# Grid_Lock.net
KiCad netlist of a schematic drawn in Altium Designer
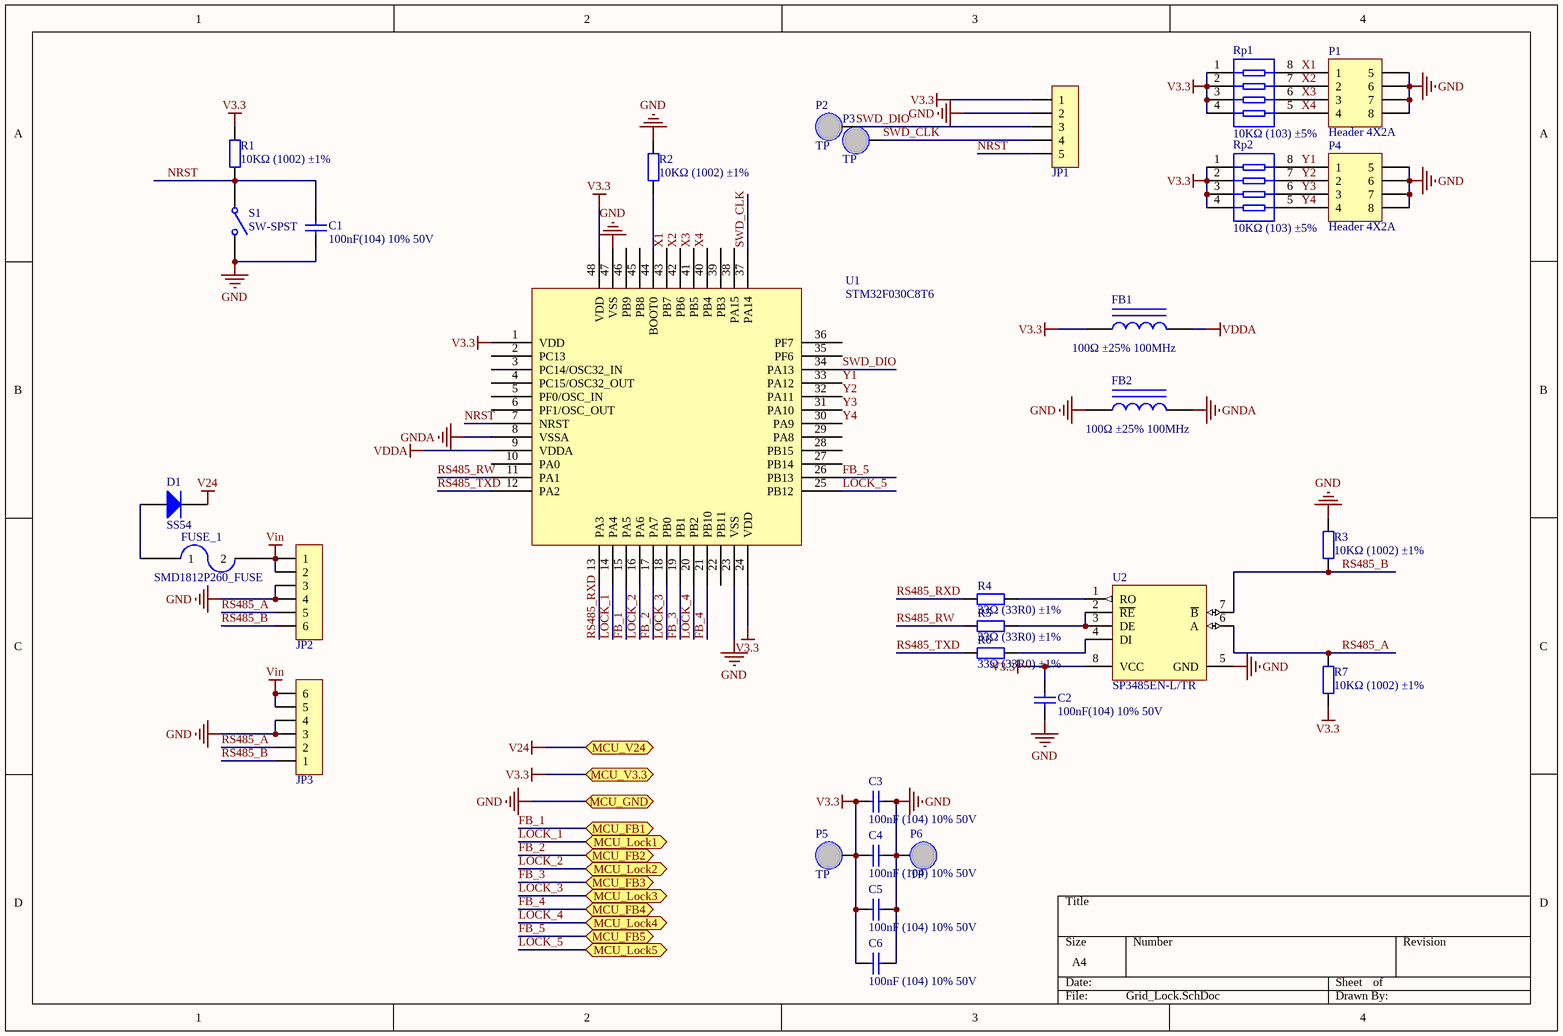
[diagram p0: Grid_Lock.SchDoc]

(export (version "E")
  (design (tool "Eeschema 10.0.6"))
  (components
    (comp (ref "C1")
      (value "100nF(104) 10% 50V")
      (footprint "0805_C")
      (description "贴片电容")
      (libsource (lib "Miscellaneous Devices LC") (part "0805 100nF(104) 10% 50V"))
    )
    (comp (ref "C2")
      (value "100nF(104) 10% 50V")
      (footprint "0805_C")
      (description "贴片电容")
      (libsource (lib "Miscellaneous Devices LC") (part "0805 100nF(104) 10% 50V"))
    )
    (comp (ref "C3")
      (value "100nF (104) 10% 50V")
      (footprint "0603_C")
      (description "贴片电容")
      (libsource (lib "Miscellaneous Devices LC") (part "0603 100nF (104) 10% 50V"))
    )
    (comp (ref "C4")
      (value "100nF (104) 10% 50V")
      (footprint "0603_C")
      (description "贴片电容")
      (libsource (lib "Miscellaneous Devices LC") (part "0603 100nF (104) 10% 50V"))
    )
    (comp (ref "C5")
      (value "100nF (104) 10% 50V")
      (footprint "0603_C")
      (description "贴片电容")
      (libsource (lib "Miscellaneous Devices LC") (part "0603 100nF (104) 10% 50V"))
    )
    (comp (ref "C6")
      (value "100nF (104) 10% 50V")
      (footprint "0603_C")
      (description "贴片电容")
      (libsource (lib "Miscellaneous Devices LC") (part "0603 100nF (104) 10% 50V"))
    )
    (comp (ref "D1")
      (value "SS54")
      (footprint "SMA(DO-214AC)_S1")
      (description "二极管")
      (libsource (lib "Miscellaneous Devices LC") (part "SMA(DO-214AC) SS54"))
    )
    (comp (ref "FB1")
      (value "100Ω ±25% 100MHz")
      (footprint "0805_L")
      (description "贴片磁珠")
      (libsource (lib "Miscellaneous Devices LC") (part "0805 100Ω 25% 100MHz"))
    )
    (comp (ref "FB2")
      (value "100Ω ±25% 100MHz")
      (footprint "0805_L")
      (description "贴片磁珠")
      (libsource (lib "Miscellaneous Devices LC") (part "0805 100Ω 25% 100MHz"))
    )
    (comp (ref "FUSE_1")
      (value "SMD1812P260_FUSE")
      (footprint "SMD1812P260")
      (libsource (lib "mylib") (part "SMD1812P260_FUSE"))
    )
    (comp (ref "JP1")
      (value "HDR-1X5")
      (footprint "XH2.54-WS-5P")
      (description "5P接插件")
      (fields (field (name "版权归属") "源创客"))
      (libsource (lib "4.5   - 接插件-脚距2.54") (part "Header 5"))
    )
    (comp (ref "JP2")
      (value "HDR-1X6")
      (footprint "XH2.54-WS-6P")
      (description "6P接插件")
      (fields (field (name "版权归属") "源创客"))
      (libsource (lib "4.5   - 接插件-脚距2.54") (part "Header 6"))
    )
    (comp (ref "JP3")
      (value "HDR-1X6")
      (footprint "XH2.54-WS-6P")
      (description "6P接插件")
      (fields (field (name "版权归属") "源创客"))
      (libsource (lib "") (part "Header 6_1"))
    )
    (comp (ref "P1")
      (value "Header 4X2A")
      (footprint "HDR2X4_CEN")
      (description "Header, 4-Pin, Dual row")
      (fields (field (name "PUBLISHER") "Altium Limited"))
      (libsource (lib "Miscellaneous Connectors") (part "Header 4X2A"))
    )
    (comp (ref "P2") (value "TP") (libsource (lib "mylib") (part "TP")))
    (comp (ref "P3") (value "TP") (libsource (lib "mylib") (part "TP")))
    (comp (ref "P4")
      (value "Header 4X2A")
      (footprint "HDR2X4_CEN")
      (description "Header, 4-Pin, Dual row")
      (fields (field (name "PUBLISHER") "Altium Limited"))
      (libsource (lib "Miscellaneous Connectors") (part "Header 4X2A"))
    )
    (comp (ref "P5") (value "TP") (libsource (lib "mylib") (part "TP")))
    (comp (ref "P6") (value "TP") (libsource (lib "mylib") (part "TP")))
    (comp (ref "R1")
      (value "10KΩ (1002) ±1%")
      (footprint "0805_R")
      (description "贴片电阻")
      (libsource (lib "Miscellaneous Devices LC") (part "0805 10KΩ (1002) 1%"))
    )
    (comp (ref "R2")
      (value "10KΩ (1002) ±1%")
      (footprint "0805_R")
      (description "贴片电阻")
      (libsource (lib "Miscellaneous Devices LC") (part "0805 10KΩ (1002) 1%"))
    )
    (comp (ref "R3")
      (value "10KΩ (1002) ±1%")
      (footprint "0805_R")
      (description "贴片电阻")
      (libsource (lib "Miscellaneous Devices LC") (part "0805 10KΩ (1002) 1%"))
    )
    (comp (ref "R4")
      (value "33Ω (33R0) ±1%")
      (footprint "0603_R")
      (description "贴片电阻")
      (libsource (lib "Miscellaneous Devices LC") (part "0603 33Ω (33R0) 1%"))
    )
    (comp (ref "R5")
      (value "33Ω (33R0) ±1%")
      (footprint "0603_R")
      (description "贴片电阻")
      (libsource (lib "Miscellaneous Devices LC") (part "0603 33Ω (33R0) 1%"))
    )
    (comp (ref "R6")
      (value "33Ω (33R0) ±1%")
      (footprint "0603_R")
      (description "贴片电阻")
      (libsource (lib "Miscellaneous Devices LC") (part "0603 33Ω (33R0) 1%"))
    )
    (comp (ref "R7")
      (value "10KΩ (1002) ±1%")
      (footprint "0805_R")
      (description "贴片电阻")
      (libsource (lib "Miscellaneous Devices LC") (part "0805 10KΩ (1002) 1%"))
    )
    (comp (ref "Rp1")
      (value "10KΩ (103) ±5%")
      (footprint "0603_Rx4")
      (description "贴片排阻")
      (libsource (lib "Miscellaneous Devices LC") (part "0603*4  10KΩ (103) 5%"))
    )
    (comp (ref "Rp2")
      (value "10KΩ (103) ±5%")
      (footprint "0603_Rx4")
      (description "贴片排阻")
      (libsource (lib "Miscellaneous Devices LC") (part "0603*4  10KΩ (103) 5%"))
    )
    (comp (ref "S1")
      (value "SW-SPST")
      (footprint "key")
      (description "Single-Pole, Single-Throw Switch")
      (fields (field (name "PUBLISHER") "Altium Limited"))
      (libsource (lib "Miscellaneous Devices") (part "SW-SPST"))
    )
    (comp (ref "U1")
      (value "STM32F030C8T6")
      (footprint "LQFP-48_7x7x05P")
      (description "ARM")
      (libsource (lib "Miscellaneous Devices LC") (part "STM32F030C8T6"))
    )
    (comp (ref "U2")
      (value "SP3485EN-L/TR")
      (footprint "SOIC-8_150mil")
      (description "RS-485/RS-422")
      (libsource (lib "Miscellaneous Devices LC") (part "SP3485EN-L/TR_[C8963]"))
    )
  )
  (nets
    (net (code "1") (name "/FB_1") (class "Default")
      (node (ref "U1") (pin "15") (pinfunction "PA5_15") (pintype "passive"))
    )
    (net (code "2") (name "/FB_2") (class "Default")
      (node (ref "U1") (pin "17") (pinfunction "PA7_17") (pintype "passive"))
    )
    (net (code "3") (name "/FB_3") (class "Default")
      (node (ref "U1") (pin "19") (pinfunction "PB1_19") (pintype "passive"))
    )
    (net (code "4") (name "/FB_4") (class "Default")
      (node (ref "U1") (pin "21") (pinfunction "PB10_21") (pintype "passive"))
    )
    (net (code "5") (name "/FB_5") (class "Default")
      (node (ref "U1") (pin "26") (pinfunction "PB13_26") (pintype "passive"))
    )
    (net (code "6") (name "/LOCK_1") (class "Default")
      (node (ref "U1") (pin "14") (pinfunction "PA4_14") (pintype "passive"))
    )
    (net (code "7") (name "/LOCK_2") (class "Default")
      (node (ref "U1") (pin "16") (pinfunction "PA6_16") (pintype "passive"))
    )
    (net (code "8") (name "/LOCK_3") (class "Default")
      (node (ref "U1") (pin "18") (pinfunction "PB0_18") (pintype "passive"))
    )
    (net (code "9") (name "/LOCK_4") (class "Default")
      (node (ref "U1") (pin "20") (pinfunction "PB2_20") (pintype "passive"))
    )
    (net (code "10") (name "/LOCK_5") (class "Default")
      (node (ref "U1") (pin "25") (pinfunction "PB12_25") (pintype "passive"))
    )
    (net (code "11") (name "/NRST") (class "Default")
      (node (ref "C1") (pin "2") (pinfunction "2_2") (pintype "passive"))
      (node (ref "JP1") (pin "5") (pinfunction "5_5") (pintype "passive"))
      (node (ref "R1") (pin "1") (pinfunction "1_1") (pintype "passive"))
      (node (ref "S1") (pin "1") (pinfunction "COMMON_1") (pintype "passive"))
      (node (ref "U1") (pin "7") (pinfunction "NRST_7") (pintype "passive"))
    )
    (net (code "12") (name "/RS485_A") (class "Default")
      (node (ref "JP2") (pin "5") (pinfunction "5_5") (pintype "passive"))
      (node (ref "JP3") (pin "2") (pinfunction "2_2") (pintype "passive"))
      (node (ref "R7") (pin "2") (pinfunction "2_2") (pintype "passive"))
      (node (ref "U2") (pin "6") (pinfunction "A_6") (pintype "bidirectional"))
    )
    (net (code "13") (name "/RS485_B") (class "Default")
      (node (ref "JP2") (pin "6") (pinfunction "6_6") (pintype "passive"))
      (node (ref "JP3") (pin "1") (pinfunction "1_1") (pintype "passive"))
      (node (ref "R3") (pin "1") (pinfunction "1_1") (pintype "passive"))
      (node (ref "U2") (pin "7") (pinfunction "~{B}_7") (pintype "bidirectional"))
    )
    (net (code "14") (name "/RS485_RW") (class "Default")
      (node (ref "R5") (pin "1") (pinfunction "1_1") (pintype "passive"))
      (node (ref "U1") (pin "11") (pinfunction "PA1_11") (pintype "passive"))
    )
    (net (code "15") (name "/RS485_RXD") (class "Default")
      (node (ref "R4") (pin "1") (pinfunction "1_1") (pintype "passive"))
      (node (ref "U1") (pin "13") (pinfunction "PA3_13") (pintype "passive"))
    )
    (net (code "16") (name "/RS485_TXD") (class "Default")
      (node (ref "R6") (pin "1") (pinfunction "1_1") (pintype "passive"))
      (node (ref "U1") (pin "12") (pinfunction "PA2_12") (pintype "passive"))
    )
    (net (code "17") (name "/SWD_CLK") (class "Default")
      (node (ref "JP1") (pin "4") (pinfunction "4_4") (pintype "passive"))
      (node (ref "P3") (pin "1") (pinfunction "1_1") (pintype "passive"))
      (node (ref "U1") (pin "37") (pinfunction "PA14_37") (pintype "passive"))
    )
    (net (code "18") (name "/SWD_DIO") (class "Default")
      (node (ref "JP1") (pin "3") (pinfunction "3_3") (pintype "passive"))
      (node (ref "P2") (pin "1") (pinfunction "1_1") (pintype "passive"))
      (node (ref "U1") (pin "34") (pinfunction "PA13_34") (pintype "passive"))
    )
    (net (code "19") (name "/X1") (class "Default")
      (node (ref "P1") (pin "1") (pinfunction "1_1") (pintype "passive"))
      (node (ref "Rp1") (pin "8") (pinfunction "8_8") (pintype "passive"))
      (node (ref "U1") (pin "43") (pinfunction "PB7_43") (pintype "passive"))
    )
    (net (code "20") (name "/X2") (class "Default")
      (node (ref "P1") (pin "2") (pinfunction "2_2") (pintype "passive"))
      (node (ref "Rp1") (pin "7") (pinfunction "7_7") (pintype "passive"))
      (node (ref "U1") (pin "42") (pinfunction "PB6_42") (pintype "passive"))
    )
    (net (code "21") (name "/X3") (class "Default")
      (node (ref "P1") (pin "3") (pinfunction "3_3") (pintype "passive"))
      (node (ref "Rp1") (pin "6") (pinfunction "6_6") (pintype "passive"))
      (node (ref "U1") (pin "41") (pinfunction "PB5_41") (pintype "passive"))
    )
    (net (code "22") (name "/X4") (class "Default")
      (node (ref "P1") (pin "4") (pinfunction "4_4") (pintype "passive"))
      (node (ref "Rp1") (pin "5") (pinfunction "5_5") (pintype "passive"))
      (node (ref "U1") (pin "40") (pinfunction "PB4_40") (pintype "passive"))
    )
    (net (code "23") (name "/Y1") (class "Default")
      (node (ref "P4") (pin "1") (pinfunction "1_1") (pintype "passive"))
      (node (ref "Rp2") (pin "8") (pinfunction "8_8") (pintype "passive"))
      (node (ref "U1") (pin "33") (pinfunction "PA12_33") (pintype "passive"))
    )
    (net (code "24") (name "/Y2") (class "Default")
      (node (ref "P4") (pin "2") (pinfunction "2_2") (pintype "passive"))
      (node (ref "Rp2") (pin "7") (pinfunction "7_7") (pintype "passive"))
      (node (ref "U1") (pin "32") (pinfunction "PA11_32") (pintype "passive"))
    )
    (net (code "25") (name "/Y3") (class "Default")
      (node (ref "P4") (pin "3") (pinfunction "3_3") (pintype "passive"))
      (node (ref "Rp2") (pin "6") (pinfunction "6_6") (pintype "passive"))
      (node (ref "U1") (pin "31") (pinfunction "PA10_31") (pintype "passive"))
    )
    (net (code "26") (name "/Y4") (class "Default")
      (node (ref "P4") (pin "4") (pinfunction "4_4") (pintype "passive"))
      (node (ref "Rp2") (pin "5") (pinfunction "5_5") (pintype "passive"))
      (node (ref "U1") (pin "30") (pinfunction "PA9_30") (pintype "passive"))
    )
    (net (code "27") (name "GND") (class "Default")
      (node (ref "C1") (pin "1") (pinfunction "1_1") (pintype "passive"))
      (node (ref "C2") (pin "1") (pinfunction "1_1") (pintype "passive"))
      (node (ref "C3") (pin "2") (pinfunction "2_2") (pintype "passive"))
      (node (ref "C4") (pin "2") (pinfunction "2_2") (pintype "passive"))
      (node (ref "C5") (pin "2") (pinfunction "2_2") (pintype "passive"))
      (node (ref "C6") (pin "2") (pinfunction "2_2") (pintype "passive"))
      (node (ref "FB2") (pin "1") (pinfunction "1_1") (pintype "passive"))
      (node (ref "JP1") (pin "2") (pinfunction "2_2") (pintype "passive"))
      (node (ref "JP2") (pin "3") (pinfunction "3_3") (pintype "passive"))
      (node (ref "JP2") (pin "4") (pinfunction "4_4") (pintype "passive"))
      (node (ref "JP3") (pin "3") (pinfunction "3_3") (pintype "passive"))
      (node (ref "JP3") (pin "4") (pinfunction "4_4") (pintype "passive"))
      (node (ref "P1") (pin "5") (pinfunction "5_5") (pintype "passive"))
      (node (ref "P1") (pin "6") (pinfunction "6_6") (pintype "passive"))
      (node (ref "P1") (pin "7") (pinfunction "7_7") (pintype "passive"))
      (node (ref "P1") (pin "8") (pinfunction "8_8") (pintype "passive"))
      (node (ref "P4") (pin "5") (pinfunction "5_5") (pintype "passive"))
      (node (ref "P4") (pin "6") (pinfunction "6_6") (pintype "passive"))
      (node (ref "P4") (pin "7") (pinfunction "7_7") (pintype "passive"))
      (node (ref "P4") (pin "8") (pinfunction "8_8") (pintype "passive"))
      (node (ref "P6") (pin "1") (pinfunction "1_1") (pintype "passive"))
      (node (ref "R2") (pin "2") (pinfunction "2_2") (pintype "passive"))
      (node (ref "R3") (pin "2") (pinfunction "2_2") (pintype "passive"))
      (node (ref "S1") (pin "2") (pinfunction "NO_2") (pintype "passive"))
      (node (ref "U1") (pin "23") (pinfunction "VSS_23") (pintype "passive"))
      (node (ref "U1") (pin "47") (pinfunction "VSS_47") (pintype "passive"))
      (node (ref "U2") (pin "5") (pinfunction "GND_5") (pintype "power_in"))
    )
    (net (code "28") (name "GNDA") (class "Default")
      (node (ref "FB2") (pin "2") (pinfunction "2_2") (pintype "passive"))
      (node (ref "U1") (pin "8") (pinfunction "VSSA_8") (pintype "passive"))
    )
    (net (code "29") (name "Net-(D1-A)") (class "Default")
      (node (ref "D1") (pin "1") (pinfunction "A_1") (pintype "passive"))
      (node (ref "FUSE_1") (pin "1") (pinfunction "1_1") (pintype "passive"))
    )
    (net (code "30") (name "Net-(U1-BOOT0)") (class "Default")
      (node (ref "R2") (pin "1") (pinfunction "1_1") (pintype "passive"))
      (node (ref "U1") (pin "44") (pinfunction "BOOT0_44") (pintype "passive"))
    )
    (net (code "31") (name "Net-(U2-DE)") (class "Default")
      (node (ref "R5") (pin "2") (pinfunction "2_2") (pintype "passive"))
      (node (ref "U2") (pin "2") (pinfunction "~{RE}_2") (pintype "passive"))
      (node (ref "U2") (pin "3") (pinfunction "DE_3") (pintype "passive"))
    )
    (net (code "32") (name "Net-(U2-DI)") (class "Default")
      (node (ref "R6") (pin "2") (pinfunction "2_2") (pintype "passive"))
      (node (ref "U2") (pin "4") (pinfunction "DI_4") (pintype "passive"))
    )
    (net (code "33") (name "Net-(U2-RO)") (class "Default")
      (node (ref "R4") (pin "2") (pinfunction "2_2") (pintype "passive"))
      (node (ref "U2") (pin "1") (pinfunction "RO_1") (pintype "output"))
    )
    (net (code "34") (name "V3.3") (class "Default")
      (node (ref "C2") (pin "2") (pinfunction "2_2") (pintype "passive"))
      (node (ref "C3") (pin "1") (pinfunction "1_1") (pintype "passive"))
      (node (ref "C4") (pin "1") (pinfunction "1_1") (pintype "passive"))
      (node (ref "C5") (pin "1") (pinfunction "1_1") (pintype "passive"))
      (node (ref "C6") (pin "1") (pinfunction "1_1") (pintype "passive"))
      (node (ref "FB1") (pin "1") (pinfunction "1_1") (pintype "passive"))
      (node (ref "JP1") (pin "1") (pinfunction "1_1") (pintype "passive"))
      (node (ref "P5") (pin "1") (pinfunction "1_1") (pintype "passive"))
      (node (ref "R1") (pin "2") (pinfunction "2_2") (pintype "passive"))
      (node (ref "R7") (pin "1") (pinfunction "1_1") (pintype "passive"))
      (node (ref "Rp1") (pin "1") (pinfunction "1_1") (pintype "passive"))
      (node (ref "Rp1") (pin "2") (pinfunction "2_2") (pintype "passive"))
      (node (ref "Rp1") (pin "3") (pinfunction "3_3") (pintype "passive"))
      (node (ref "Rp1") (pin "4") (pinfunction "4_4") (pintype "passive"))
      (node (ref "Rp2") (pin "1") (pinfunction "1_1") (pintype "passive"))
      (node (ref "Rp2") (pin "2") (pinfunction "2_2") (pintype "passive"))
      (node (ref "Rp2") (pin "3") (pinfunction "3_3") (pintype "passive"))
      (node (ref "Rp2") (pin "4") (pinfunction "4_4") (pintype "passive"))
      (node (ref "U1") (pin "1") (pinfunction "VDD_1") (pintype "passive"))
      (node (ref "U1") (pin "24") (pinfunction "VDD_24") (pintype "passive"))
      (node (ref "U1") (pin "48") (pinfunction "VDD_48") (pintype "passive"))
      (node (ref "U2") (pin "8") (pinfunction "VCC_8") (pintype "power_in"))
    )
    (net (code "35") (name "V24") (class "Default")
      (node (ref "D1") (pin "2") (pinfunction "K_2") (pintype "passive"))
    )
    (net (code "36") (name "VDDA") (class "Default")
      (node (ref "FB1") (pin "2") (pinfunction "2_2") (pintype "passive"))
      (node (ref "U1") (pin "9") (pinfunction "VDDA_9") (pintype "passive"))
    )
    (net (code "37") (name "Vin") (class "Default")
      (node (ref "FUSE_1") (pin "2") (pinfunction "2_2") (pintype "passive"))
      (node (ref "JP2") (pin "1") (pinfunction "1_1") (pintype "passive"))
      (node (ref "JP2") (pin "2") (pinfunction "2_2") (pintype "passive"))
      (node (ref "JP3") (pin "5") (pinfunction "5_5") (pintype "passive"))
      (node (ref "JP3") (pin "6") (pinfunction "6_6") (pintype "passive"))
    )
    (net (code "38") (name "unconnected-(U1-PA0-Pad10)") (class "Default")
      (node (ref "U1") (pin "10") (pinfunction "PA0_10") (pintype "passive"))
    )
    (net (code "39") (name "unconnected-(U1-PA8-Pad29)") (class "Default")
      (node (ref "U1") (pin "29") (pinfunction "PA8_29") (pintype "passive"))
    )
    (net (code "40") (name "unconnected-(U1-PA15-Pad38)") (class "Default")
      (node (ref "U1") (pin "38") (pinfunction "PA15_38") (pintype "passive"))
    )
    (net (code "41") (name "unconnected-(U1-PB3-Pad39)") (class "Default")
      (node (ref "U1") (pin "39") (pinfunction "PB3_39") (pintype "passive"))
    )
    (net (code "42") (name "unconnected-(U1-PB8-Pad45)") (class "Default")
      (node (ref "U1") (pin "45") (pinfunction "PB8_45") (pintype "passive"))
    )
    (net (code "43") (name "unconnected-(U1-PB9-Pad46)") (class "Default")
      (node (ref "U1") (pin "46") (pinfunction "PB9_46") (pintype "passive"))
    )
    (net (code "44") (name "unconnected-(U1-PB11-Pad22)") (class "Default")
      (node (ref "U1") (pin "22") (pinfunction "PB11_22") (pintype "passive"))
    )
    (net (code "45") (name "unconnected-(U1-PB14-Pad27)") (class "Default")
      (node (ref "U1") (pin "27") (pinfunction "PB14_27") (pintype "passive"))
    )
    (net (code "46") (name "unconnected-(U1-PB15-Pad28)") (class "Default")
      (node (ref "U1") (pin "28") (pinfunction "PB15_28") (pintype "passive"))
    )
    (net (code "47") (name "unconnected-(U1-PC13-Pad2)") (class "Default")
      (node (ref "U1") (pin "2") (pinfunction "PC13_2") (pintype "passive"))
    )
    (net (code "48") (name "unconnected-(U1-PC14{slash}OSC32_IN-Pad3)") (class "Default")
      (node (ref "U1") (pin "3") (pinfunction "PC14/OSC32_IN_3") (pintype "passive"))
    )
    (net (code "49") (name "unconnected-(U1-PC15{slash}OSC32_OUT-Pad4)") (class "Default")
      (node (ref "U1") (pin "4") (pinfunction "PC15/OSC32_OUT_4") (pintype "passive"))
    )
    (net (code "50") (name "unconnected-(U1-PF0{slash}OSC_IN-Pad5)") (class "Default")
      (node (ref "U1") (pin "5") (pinfunction "PF0/OSC_IN_5") (pintype "passive"))
    )
    (net (code "51") (name "unconnected-(U1-PF1{slash}OSC_OUT-Pad6)") (class "Default")
      (node (ref "U1") (pin "6") (pinfunction "PF1/OSC_OUT_6") (pintype "passive"))
    )
    (net (code "52") (name "unconnected-(U1-PF6-Pad35)") (class "Default")
      (node (ref "U1") (pin "35") (pinfunction "PF6_35") (pintype "passive"))
    )
    (net (code "53") (name "unconnected-(U1-PF7-Pad36)") (class "Default")
      (node (ref "U1") (pin "36") (pinfunction "PF7_36") (pintype "passive"))
    )
  )
)
